# pixel.net
KiCad netlist of a schematic drawn in EAGLE
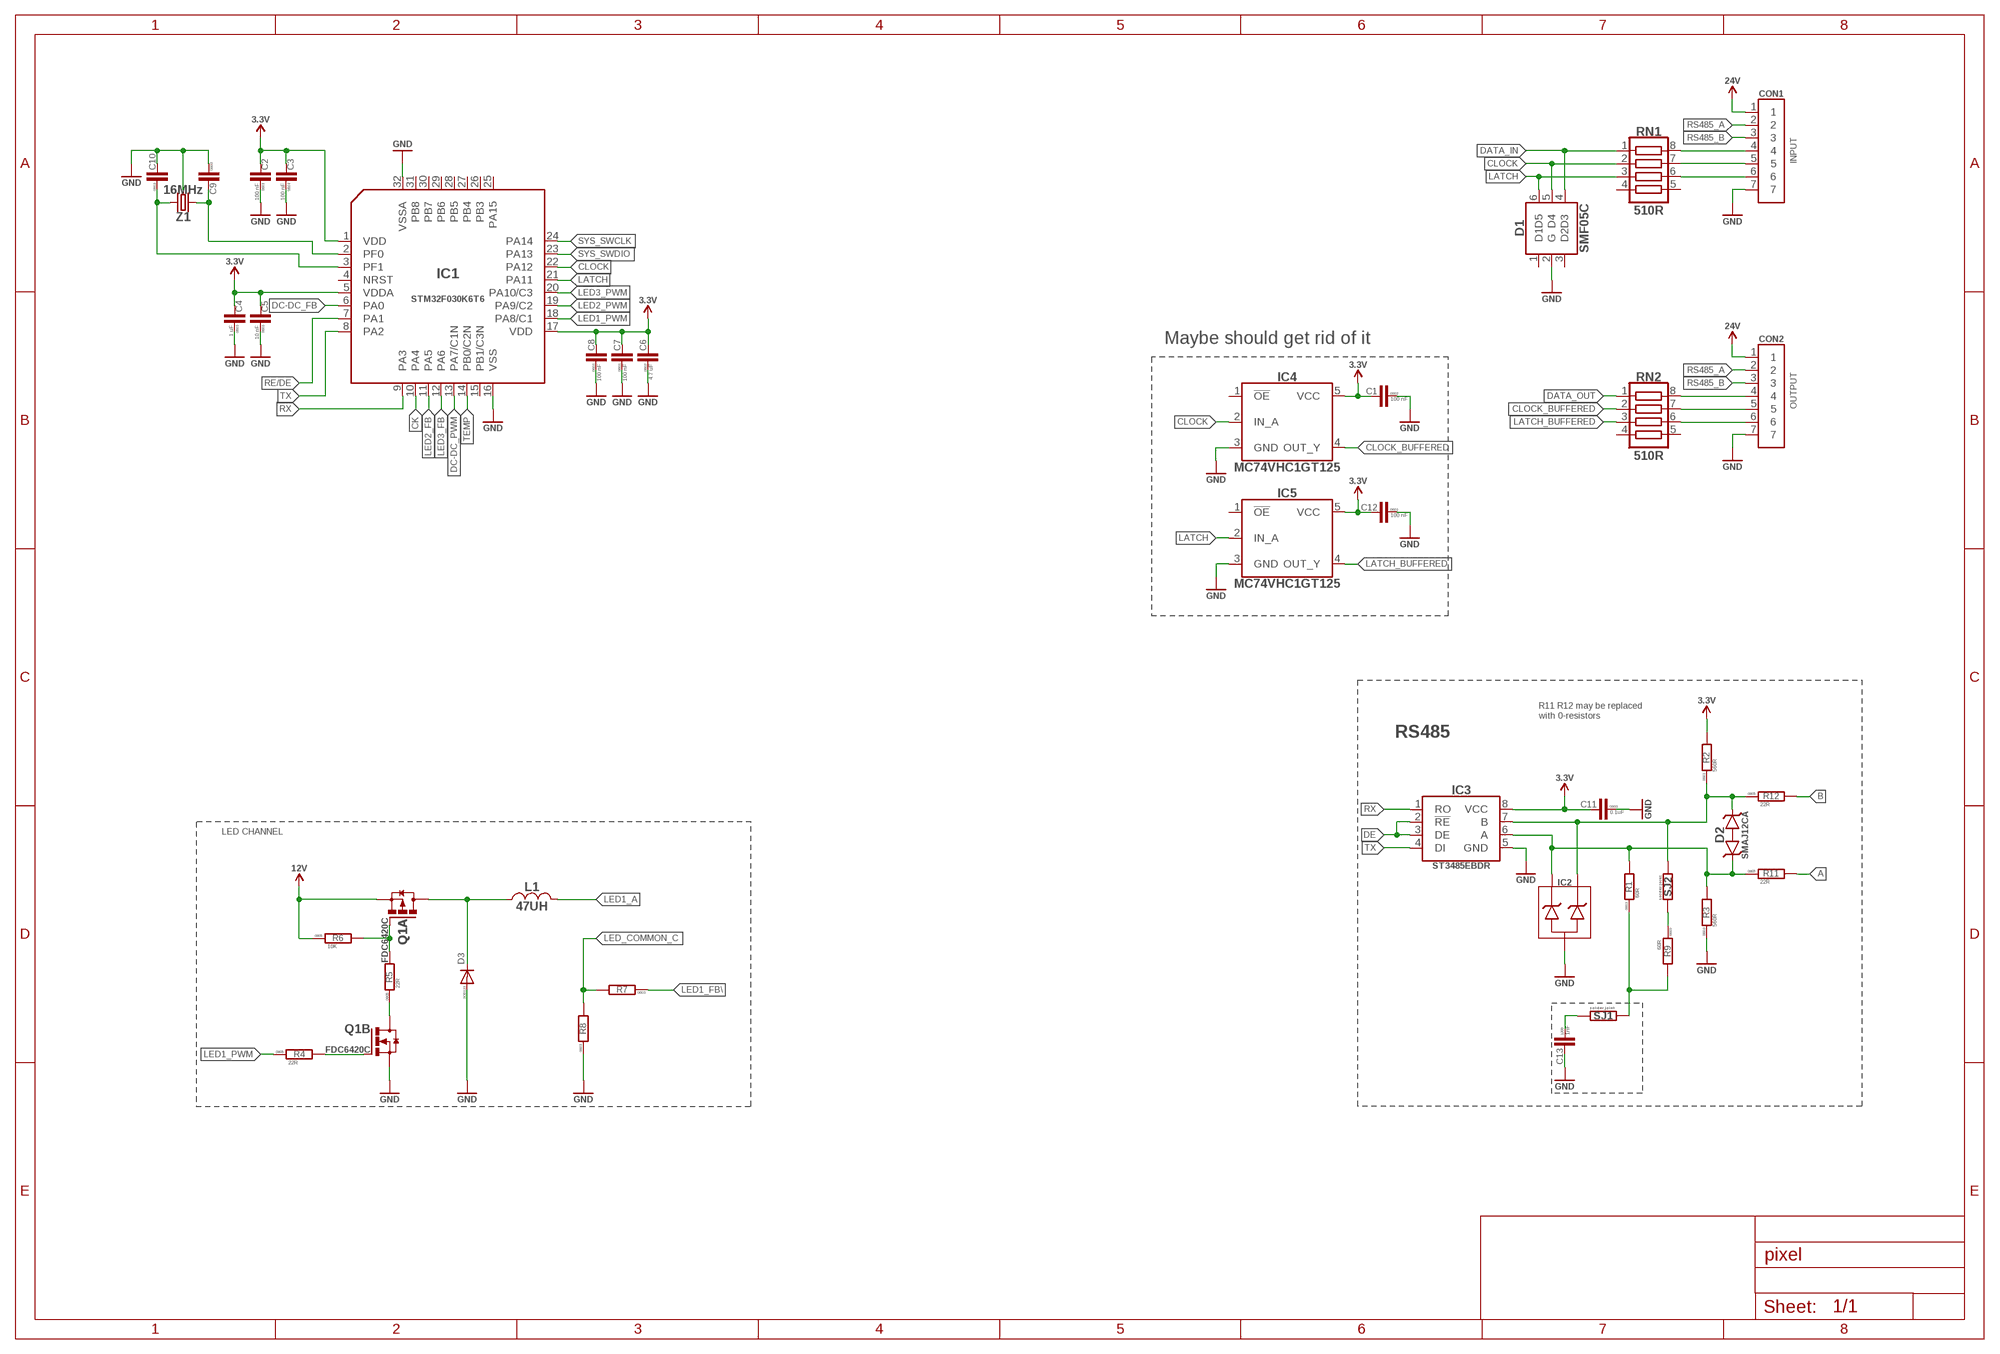
[diagram p0: schematic, sheet 1]

(export (version "E")
  (design (tool "Eeschema 10.0.6"))
  (components
    (comp (ref "C1")
      (value "100 nF")
      (footprint "eagle-import:C0603")
      (libsource (lib "eagle-import") (part "C-0603"))
    )
    (comp (ref "C2")
      (value "100 nF")
      (footprint "eagle-import:C0603")
      (libsource (lib "eagle-import") (part "C-0603"))
    )
    (comp (ref "C3")
      (value "100 nF")
      (footprint "eagle-import:C0603")
      (libsource (lib "eagle-import") (part "C-0603"))
    )
    (comp (ref "C4")
      (value "1 uF")
      (footprint "eagle-import:C0603")
      (libsource (lib "eagle-import") (part "C-0603"))
    )
    (comp (ref "C5")
      (value "10 nF")
      (footprint "eagle-import:C0603")
      (libsource (lib "eagle-import") (part "C-0603"))
    )
    (comp (ref "C6")
      (value "4.7 uF")
      (footprint "eagle-import:C0603")
      (libsource (lib "eagle-import") (part "C-0603"))
    )
    (comp (ref "C7")
      (value "100 nF")
      (footprint "eagle-import:C0603")
      (libsource (lib "eagle-import") (part "C-0603"))
    )
    (comp (ref "C8")
      (value "100 nF")
      (footprint "eagle-import:C0603")
      (libsource (lib "eagle-import") (part "C-0603"))
    )
    (comp (ref "C9")
      (value "C-0603")
      (footprint "eagle-import:C0603")
      (libsource (lib "eagle-import") (part "C-0603"))
    )
    (comp (ref "C10")
      (value "C-0603")
      (footprint "eagle-import:C0603")
      (libsource (lib "eagle-import") (part "C-0603"))
    )
    (comp (ref "C11")
      (value "0.1uF")
      (footprint "eagle-import:C0603")
      (libsource (lib "eagle-import") (part "C-0603"))
    )
    (comp (ref "C12")
      (value "100 nF")
      (footprint "eagle-import:C0603")
      (libsource (lib "eagle-import") (part "C-0603"))
    )
    (comp (ref "C13")
      (value "1nF")
      (footprint "eagle-import:C1206")
      (fields (field (name "ASSEMBLY") "SPECIAL"))
      (libsource (lib "eagle-import") (part "C-1206"))
    )
    (comp (ref "CON1")
      (value "DS1066-07M-SIDE")
      (footprint "eagle-import:DS1066-08M_SIDE")
      (libsource (lib "eagle-import") (part "DS1066-07M-SIDE"))
    )
    (comp (ref "CON2")
      (value "DS1066-07M-SIDE")
      (footprint "eagle-import:DS1066-08M_SIDE")
      (libsource (lib "eagle-import") (part "DS1066-07M-SIDE"))
    )
    (comp (ref "D1")
      (value "SMF05C")
      (footprint "eagle-import:SC70_6L")
      (fields (field (name "MANF") "Semtech Corporation"))
      (libsource (lib "eagle-import") (part "SMF05C"))
    )
    (comp (ref "D2")
      (value "SMAJ12A")
      (footprint "eagle-import:SMA")
      (fields (field (name "MANF") "Bourns Inc"))
      (libsource (lib "eagle-import") (part "SMAJ12A"))
    )
    (comp (ref "D3")
      (value "DIODE-SOD123")
      (footprint "eagle-import:SOD123")
      (libsource (lib "eagle-import") (part "DIODE-SOD123"))
    )
    (comp (ref "IC1")
      (value "STM32F030K6TX-LQFP32(7X7)")
      (footprint "eagle-import:LQFP32-7X7")
      (fields (field (name "MANF") "STMicroelectronics"))
      (libsource (lib "eagle-import") (part "STM32F030K6TX-LQFP32(7X7)"))
    )
    (comp (ref "IC2")
      (value "ESDA6V1L")
      (footprint "eagle-import:SOT23")
      (fields (field (name "MANF") "STMicroelectronics"))
      (libsource (lib "eagle-import") (part "ESDA6V1L"))
    )
    (comp (ref "IC3")
      (value "ST3485SOIC8")
      (footprint "eagle-import:SOIC8")
      (fields (field (name "MANF") "STMicroelectronics"))
      (libsource (lib "eagle-import") (part "ST3485SOIC8"))
    )
    (comp (ref "IC4")
      (value "MC74VHC1GT125")
      (footprint "eagle-import:SOT23-5")
      (fields (field (name "MANF") "ON Semiconductor"))
      (libsource (lib "eagle-import") (part "MC74VHC1GT125"))
    )
    (comp (ref "IC5")
      (value "MC74VHC1GT125")
      (footprint "eagle-import:SOT23-5")
      (fields (field (name "MANF") "ON Semiconductor"))
      (libsource (lib "eagle-import") (part "MC74VHC1GT125"))
    )
    (comp (ref "L1")
      (value "47UH")
      (footprint "eagle-import:SDR0604")
      (fields (field (name "MANF") "Bourns Inc"))
      (libsource (lib "eagle-import") (part "SDR0604-470KL"))
    )
    (comp (ref "Q1")
      (value "FDC6420C")
      (footprint "eagle-import:SOT23-6")
      (fields (field (name "MANF") "Fairchild"))
      (libsource (lib "eagle-import") (part "FDC6420C"))
    )
    (comp (ref "R1")
      (value "60R")
      (footprint "eagle-import:R0603")
      (libsource (lib "eagle-import") (part "R-0603"))
    )
    (comp (ref "R2")
      (value "560R")
      (footprint "eagle-import:R0603")
      (libsource (lib "eagle-import") (part "R-0603"))
    )
    (comp (ref "R3")
      (value "560R")
      (footprint "eagle-import:R0603")
      (libsource (lib "eagle-import") (part "R-0603"))
    )
    (comp (ref "R4")
      (value "22R")
      (footprint "eagle-import:R0805")
      (libsource (lib "eagle-import") (part "R-0805"))
    )
    (comp (ref "R5")
      (value "22R")
      (footprint "eagle-import:R0805")
      (libsource (lib "eagle-import") (part "R-0805"))
    )
    (comp (ref "R6")
      (value "10K")
      (footprint "eagle-import:R0805")
      (libsource (lib "eagle-import") (part "R-0805"))
    )
    (comp (ref "R7")
      (value "R-0603")
      (footprint "eagle-import:R0603")
      (libsource (lib "eagle-import") (part "R-0603"))
    )
    (comp (ref "R8")
      (value "R-0603")
      (footprint "eagle-import:R0603")
      (libsource (lib "eagle-import") (part "R-0603"))
    )
    (comp (ref "R9")
      (value "60R")
      (footprint "eagle-import:R0603")
      (libsource (lib "eagle-import") (part "R-0603"))
    )
    (comp (ref "R11")
      (value "22R")
      (footprint "eagle-import:R0805")
      (libsource (lib "eagle-import") (part "R-0805"))
    )
    (comp (ref "R12")
      (value "22R")
      (footprint "eagle-import:R0805")
      (libsource (lib "eagle-import") (part "R-0805"))
    )
    (comp (ref "RN1")
      (value "510R")
      (footprint "eagle-import:CAT16-J4")
      (fields
        (field (name "DIGIKEY#") "CAT16-511J4LF-ND")
        (field (name "MANF") "Bourns Inc")
        (field (name "MANF#") "CAT16-511J4LF")
      )
      (libsource (lib "eagle-import") (part "RESISTOR_ARRAY"))
    )
    (comp (ref "RN2")
      (value "510R")
      (footprint "eagle-import:CAT16-J4")
      (fields
        (field (name "DIGIKEY#") "CAT16-511J4LF-ND")
        (field (name "MANF") "Bourns Inc")
        (field (name "MANF#") "CAT16-511J4LF")
      )
      (libsource (lib "eagle-import") (part "RESISTOR_ARRAY"))
    )
    (comp (ref "SJ1")
      (value "SOLDER_JOINT")
      (footprint "eagle-import:RES_0")
      (libsource (lib "eagle-import") (part "SOLDER_JOINT"))
    )
    (comp (ref "SJ2")
      (value "SOLDER_JOINT")
      (footprint "eagle-import:RES_0")
      (libsource (lib "eagle-import") (part "SOLDER_JOINT"))
    )
    (comp (ref "Z1")
      (value "16MHz")
      (footprint "eagle-import:OSCILLATOR-3.2X2.5")
      (fields (field (name "MANF") "AVX Corp/Kyocera Corp"))
      (libsource (lib "eagle-import") (part "CRYSTAL-3.2X2.5-4P"))
    )
  )
  (nets
    (net (code "1") (name "3.3V") (class "Default")
      (node (ref "C1") (pin "2") (pinfunction "2_2") (pintype "passive"))
      (node (ref "C11") (pin "2") (pinfunction "2_2") (pintype "passive"))
      (node (ref "C12") (pin "2") (pinfunction "2_2") (pintype "passive"))
      (node (ref "C2") (pin "2") (pinfunction "2_2") (pintype "passive"))
      (node (ref "C3") (pin "2") (pinfunction "2_2") (pintype "passive"))
      (node (ref "C4") (pin "2") (pinfunction "2_2") (pintype "passive"))
      (node (ref "C5") (pin "2") (pinfunction "2_2") (pintype "passive"))
      (node (ref "C6") (pin "2") (pinfunction "2_2") (pintype "passive"))
      (node (ref "C7") (pin "2") (pinfunction "2_2") (pintype "passive"))
      (node (ref "C8") (pin "2") (pinfunction "2_2") (pintype "passive"))
      (node (ref "IC1") (pin "1") (pinfunction "VDD_1") (pintype "bidirectional"))
      (node (ref "IC1") (pin "17") (pinfunction "VDD_17") (pintype "bidirectional"))
      (node (ref "IC1") (pin "5") (pinfunction "VDDA_5") (pintype "bidirectional"))
      (node (ref "IC3") (pin "8") (pinfunction "VCC_8") (pintype "bidirectional"))
      (node (ref "IC4") (pin "5") (pinfunction "VCC_5") (pintype "bidirectional"))
      (node (ref "IC5") (pin "5") (pinfunction "VCC_5") (pintype "bidirectional"))
      (node (ref "R2") (pin "2") (pinfunction "2_2") (pintype "passive"))
    )
    (net (code "2") (name "12V") (class "Default")
      (node (ref "Q1") (pin "4") (pinfunction "S_4") (pintype "passive"))
      (node (ref "R6") (pin "1") (pinfunction "1_1") (pintype "passive"))
    )
    (net (code "3") (name "24V") (class "Default")
      (node (ref "CON1") (pin "1") (pinfunction "1_1") (pintype "bidirectional"))
      (node (ref "CON2") (pin "1") (pinfunction "1_1") (pintype "bidirectional"))
    )
    (net (code "4") (name "A") (class "Default")
      (node (ref "D2") (pin "A") (pinfunction "P$1_A") (pintype "bidirectional"))
      (node (ref "IC2") (pin "2") (pinfunction "C1_2") (pintype "bidirectional"))
      (node (ref "IC3") (pin "6") (pinfunction "A_6") (pintype "bidirectional"))
      (node (ref "R1") (pin "2") (pinfunction "2_2") (pintype "passive"))
      (node (ref "R11") (pin "1") (pinfunction "1_1") (pintype "passive"))
      (node (ref "R11") (pin "2") (pinfunction "2_2") (pintype "passive"))
      (node (ref "R3") (pin "2") (pinfunction "2_2") (pintype "passive"))
    )
    (net (code "5") (name "B") (class "Default")
      (node (ref "D2") (pin "C") (pinfunction "P$2_C") (pintype "bidirectional"))
      (node (ref "IC2") (pin "3") (pinfunction "C2_3") (pintype "bidirectional"))
      (node (ref "IC3") (pin "7") (pinfunction "B_7") (pintype "bidirectional"))
      (node (ref "R12") (pin "1") (pinfunction "1_1") (pintype "passive"))
      (node (ref "R12") (pin "2") (pinfunction "2_2") (pintype "passive"))
      (node (ref "R2") (pin "1") (pinfunction "1_1") (pintype "passive"))
      (node (ref "SJ2") (pin "1") (pinfunction "1_1") (pintype "passive"))
    )
    (net (code "6") (name "CK") (class "Default")
      (node (ref "IC1") (pin "10") (pinfunction "PA4_10") (pintype "bidirectional"))
    )
    (net (code "7") (name "CLOCK") (class "Default")
      (node (ref "D1") (pin "5") (pinfunction "D4_5") (pintype "bidirectional"))
      (node (ref "IC1") (pin "22") (pinfunction "PA12_22") (pintype "bidirectional"))
      (node (ref "IC4") (pin "2") (pinfunction "IN_A_2") (pintype "bidirectional"))
      (node (ref "RN1") (pin "2") (pinfunction "2_2") (pintype "passive"))
    )
    (net (code "8") (name "CLOCK_BUFFERED") (class "Default")
      (node (ref "IC4") (pin "4") (pinfunction "OUT_Y_4") (pintype "bidirectional"))
      (node (ref "RN2") (pin "2") (pinfunction "2_2") (pintype "passive"))
    )
    (net (code "9") (name "DATA_IN") (class "Default")
      (node (ref "D1") (pin "4") (pinfunction "D3_4") (pintype "bidirectional"))
      (node (ref "RN1") (pin "1") (pinfunction "1_1") (pintype "passive"))
    )
    (net (code "10") (name "DATA_OUT") (class "Default")
      (node (ref "RN2") (pin "1") (pinfunction "1_1") (pintype "passive"))
    )
    (net (code "11") (name "DC-DC_FB") (class "Default")
      (node (ref "IC1") (pin "6") (pinfunction "PA0_6") (pintype "bidirectional"))
    )
    (net (code "12") (name "DC-DC_PWM") (class "Default")
      (node (ref "IC1") (pin "13") (pinfunction "PA7/C1N_13") (pintype "bidirectional"))
    )
    (net (code "13") (name "DE") (class "Default")
      (node (ref "IC3") (pin "2") (pinfunction "~{RE}_2") (pintype "bidirectional"))
      (node (ref "IC3") (pin "3") (pinfunction "DE_3") (pintype "bidirectional"))
    )
    (net (code "14") (name "GND") (class "Default")
      (node (ref "C1") (pin "1") (pinfunction "1_1") (pintype "passive"))
      (node (ref "C10") (pin "2") (pinfunction "2_2") (pintype "passive"))
      (node (ref "C11") (pin "1") (pinfunction "1_1") (pintype "passive"))
      (node (ref "C12") (pin "1") (pinfunction "1_1") (pintype "passive"))
      (node (ref "C13") (pin "P$2") (pinfunction "2_P$2") (pintype "passive"))
      (node (ref "C2") (pin "1") (pinfunction "1_1") (pintype "passive"))
      (node (ref "C3") (pin "1") (pinfunction "1_1") (pintype "passive"))
      (node (ref "C4") (pin "1") (pinfunction "1_1") (pintype "passive"))
      (node (ref "C5") (pin "1") (pinfunction "1_1") (pintype "passive"))
      (node (ref "C6") (pin "1") (pinfunction "1_1") (pintype "passive"))
      (node (ref "C7") (pin "1") (pinfunction "1_1") (pintype "passive"))
      (node (ref "C8") (pin "1") (pinfunction "1_1") (pintype "passive"))
      (node (ref "C9") (pin "1") (pinfunction "1_1") (pintype "passive"))
      (node (ref "CON1") (pin "7") (pinfunction "7_7") (pintype "bidirectional"))
      (node (ref "CON2") (pin "7") (pinfunction "7_7") (pintype "bidirectional"))
      (node (ref "D1") (pin "2") (pinfunction "G_2") (pintype "bidirectional"))
      (node (ref "D3") (pin "A") (pinfunction "A_A") (pintype "passive"))
      (node (ref "IC1") (pin "16") (pinfunction "VSS_16") (pintype "bidirectional"))
      (node (ref "IC1") (pin "32") (pinfunction "VSSA_32") (pintype "bidirectional"))
      (node (ref "IC2") (pin "1") (pinfunction "A_1") (pintype "bidirectional"))
      (node (ref "IC3") (pin "5") (pinfunction "GND_5") (pintype "bidirectional"))
      (node (ref "IC4") (pin "3") (pinfunction "GND_3") (pintype "bidirectional"))
      (node (ref "IC5") (pin "3") (pinfunction "GND_3") (pintype "bidirectional"))
      (node (ref "Q1") (pin "5") (pinfunction "S_5") (pintype "passive"))
      (node (ref "R3") (pin "1") (pinfunction "1_1") (pintype "passive"))
      (node (ref "R8") (pin "1") (pinfunction "1_1") (pintype "passive"))
      (node (ref "Z1") (pin "2") (pinfunction "GND_2") (pintype "bidirectional"))
      (node (ref "Z1") (pin "4") (pinfunction "GND_4") (pintype "bidirectional"))
    )
    (net (code "15") (name "LATCH") (class "Default")
      (node (ref "D1") (pin "6") (pinfunction "D5_6") (pintype "bidirectional"))
      (node (ref "IC1") (pin "21") (pinfunction "PA11_21") (pintype "bidirectional"))
      (node (ref "IC5") (pin "2") (pinfunction "IN_A_2") (pintype "bidirectional"))
      (node (ref "RN1") (pin "3") (pinfunction "3_3") (pintype "passive"))
    )
    (net (code "16") (name "LATCH_BUFFERED") (class "Default")
      (node (ref "IC5") (pin "4") (pinfunction "OUT_Y_4") (pintype "bidirectional"))
      (node (ref "RN2") (pin "3") (pinfunction "3_3") (pintype "passive"))
    )
    (net (code "17") (name "LED1_A") (class "Default")
      (node (ref "L1") (pin "2") (pinfunction "2_2") (pintype "passive"))
    )
    (net (code "18") (name "LED1_FB\\") (class "Default")
      (node (ref "R7") (pin "1") (pinfunction "1_1") (pintype "passive"))
    )
    (net (code "19") (name "LED1_PWM") (class "Default")
      (node (ref "IC1") (pin "18") (pinfunction "PA8/C1_18") (pintype "bidirectional"))
      (node (ref "R4") (pin "1") (pinfunction "1_1") (pintype "passive"))
    )
    (net (code "20") (name "LED2_FB") (class "Default")
      (node (ref "IC1") (pin "11") (pinfunction "PA5_11") (pintype "bidirectional"))
    )
    (net (code "21") (name "LED2_PWM") (class "Default")
      (node (ref "IC1") (pin "19") (pinfunction "PA9/C2_19") (pintype "bidirectional"))
    )
    (net (code "22") (name "LED3_FB") (class "Default")
      (node (ref "IC1") (pin "12") (pinfunction "PA6_12") (pintype "bidirectional"))
    )
    (net (code "23") (name "LED3_PWM") (class "Default")
      (node (ref "IC1") (pin "20") (pinfunction "PA10/C3_20") (pintype "bidirectional"))
    )
    (net (code "24") (name "LED_COMMON_C") (class "Default")
      (node (ref "R7") (pin "2") (pinfunction "2_2") (pintype "passive"))
      (node (ref "R8") (pin "2") (pinfunction "2_2") (pintype "passive"))
    )
    (net (code "25") (name "Net-(C13-1)") (class "Default")
      (node (ref "C13") (pin "P$1") (pinfunction "1_P$1") (pintype "passive"))
      (node (ref "SJ1") (pin "2") (pinfunction "2_2") (pintype "passive"))
    )
    (net (code "26") (name "Net-(CON1-Pad4)") (class "Default")
      (node (ref "CON1") (pin "4") (pinfunction "4_4") (pintype "bidirectional"))
      (node (ref "RN1") (pin "8") (pinfunction "8_8") (pintype "passive"))
    )
    (net (code "27") (name "Net-(CON1-Pad5)") (class "Default")
      (node (ref "CON1") (pin "5") (pinfunction "5_5") (pintype "bidirectional"))
      (node (ref "RN1") (pin "7") (pinfunction "7_7") (pintype "passive"))
    )
    (net (code "28") (name "Net-(CON1-Pad6)") (class "Default")
      (node (ref "CON1") (pin "6") (pinfunction "6_6") (pintype "bidirectional"))
      (node (ref "RN1") (pin "6") (pinfunction "6_6") (pintype "passive"))
    )
    (net (code "29") (name "Net-(CON2-Pad4)") (class "Default")
      (node (ref "CON2") (pin "4") (pinfunction "4_4") (pintype "bidirectional"))
      (node (ref "RN2") (pin "8") (pinfunction "8_8") (pintype "passive"))
    )
    (net (code "30") (name "Net-(CON2-Pad5)") (class "Default")
      (node (ref "CON2") (pin "5") (pinfunction "5_5") (pintype "bidirectional"))
      (node (ref "RN2") (pin "7") (pinfunction "7_7") (pintype "passive"))
    )
    (net (code "31") (name "Net-(CON2-Pad6)") (class "Default")
      (node (ref "CON2") (pin "6") (pinfunction "6_6") (pintype "bidirectional"))
      (node (ref "RN2") (pin "6") (pinfunction "6_6") (pintype "passive"))
    )
    (net (code "32") (name "Net-(IC1-PF0)") (class "Default")
      (node (ref "C9") (pin "2") (pinfunction "2_2") (pintype "passive"))
      (node (ref "IC1") (pin "2") (pinfunction "PF0_2") (pintype "bidirectional"))
      (node (ref "Z1") (pin "1") (pinfunction "1_1") (pintype "passive"))
    )
    (net (code "33") (name "Net-(IC1-PF1)") (class "Default")
      (node (ref "C10") (pin "1") (pinfunction "1_1") (pintype "passive"))
      (node (ref "IC1") (pin "3") (pinfunction "PF1_3") (pintype "bidirectional"))
      (node (ref "Z1") (pin "3") (pinfunction "2_3") (pintype "passive"))
    )
    (net (code "34") (name "Net-(Q1A-D)") (class "Default")
      (node (ref "D3") (pin "C") (pinfunction "C_C") (pintype "passive"))
      (node (ref "L1") (pin "1") (pinfunction "1_1") (pintype "passive"))
      (node (ref "Q1") (pin "2") (pinfunction "D_2") (pintype "passive"))
    )
    (net (code "35") (name "Net-(Q1A-G)") (class "Default")
      (node (ref "Q1") (pin "3") (pinfunction "G_3") (pintype "passive"))
      (node (ref "R5") (pin "2") (pinfunction "2_2") (pintype "passive"))
      (node (ref "R6") (pin "2") (pinfunction "2_2") (pintype "passive"))
    )
    (net (code "36") (name "Net-(Q1B-D)") (class "Default")
      (node (ref "Q1") (pin "6") (pinfunction "D_6") (pintype "passive"))
      (node (ref "R5") (pin "1") (pinfunction "1_1") (pintype "passive"))
    )
    (net (code "37") (name "Net-(Q1B-G)") (class "Default")
      (node (ref "Q1") (pin "1") (pinfunction "G_1") (pintype "passive"))
      (node (ref "R4") (pin "2") (pinfunction "2_2") (pintype "passive"))
    )
    (net (code "38") (name "Net-(R1-Pad1)") (class "Default")
      (node (ref "R1") (pin "1") (pinfunction "1_1") (pintype "passive"))
      (node (ref "R9") (pin "2") (pinfunction "2_2") (pintype "passive"))
      (node (ref "SJ1") (pin "1") (pinfunction "1_1") (pintype "passive"))
    )
    (net (code "39") (name "Net-(R9-Pad1)") (class "Default")
      (node (ref "R9") (pin "1") (pinfunction "1_1") (pintype "passive"))
      (node (ref "SJ2") (pin "2") (pinfunction "2_2") (pintype "passive"))
    )
    (net (code "40") (name "RE{slash}DE") (class "Default")
      (node (ref "IC1") (pin "7") (pinfunction "PA1_7") (pintype "bidirectional"))
    )
    (net (code "41") (name "RS485_A") (class "Default")
      (node (ref "CON1") (pin "2") (pinfunction "2_2") (pintype "bidirectional"))
      (node (ref "CON2") (pin "2") (pinfunction "2_2") (pintype "bidirectional"))
    )
    (net (code "42") (name "RS485_B") (class "Default")
      (node (ref "CON1") (pin "3") (pinfunction "3_3") (pintype "bidirectional"))
      (node (ref "CON2") (pin "3") (pinfunction "3_3") (pintype "bidirectional"))
    )
    (net (code "43") (name "RX") (class "Default")
      (node (ref "IC1") (pin "9") (pinfunction "PA3_9") (pintype "bidirectional"))
      (node (ref "IC3") (pin "1") (pinfunction "RO_1") (pintype "bidirectional"))
    )
    (net (code "44") (name "SYS_SWCLK") (class "Default")
      (node (ref "IC1") (pin "24") (pinfunction "PA14_24") (pintype "bidirectional"))
    )
    (net (code "45") (name "SYS_SWDIO") (class "Default")
      (node (ref "IC1") (pin "23") (pinfunction "PA13_23") (pintype "bidirectional"))
    )
    (net (code "46") (name "TEMP") (class "Default")
      (node (ref "IC1") (pin "14") (pinfunction "PB0/C2N_14") (pintype "bidirectional"))
    )
    (net (code "47") (name "TX") (class "Default")
      (node (ref "IC1") (pin "8") (pinfunction "PA2_8") (pintype "bidirectional"))
      (node (ref "IC3") (pin "4") (pinfunction "DI_4") (pintype "bidirectional"))
    )
    (net (code "48") (name "unconnected-(D1-D1-Pad1)") (class "Default")
      (node (ref "D1") (pin "1") (pinfunction "D1_1") (pintype "bidirectional"))
    )
    (net (code "49") (name "unconnected-(D1-D2-Pad3)") (class "Default")
      (node (ref "D1") (pin "3") (pinfunction "D2_3") (pintype "bidirectional"))
    )
    (net (code "50") (name "unconnected-(IC1-NRST-Pad4)") (class "Default")
      (node (ref "IC1") (pin "4") (pinfunction "NRST_4") (pintype "bidirectional"))
    )
    (net (code "51") (name "unconnected-(IC1-PA15-Pad25)") (class "Default")
      (node (ref "IC1") (pin "25") (pinfunction "PA15_25") (pintype "bidirectional"))
    )
    (net (code "52") (name "unconnected-(IC1-PB1{slash}C3N-Pad15)") (class "Default")
      (node (ref "IC1") (pin "15") (pinfunction "PB1/C3N_15") (pintype "bidirectional"))
    )
    (net (code "53") (name "unconnected-(IC1-PB3-Pad26)") (class "Default")
      (node (ref "IC1") (pin "26") (pinfunction "PB3_26") (pintype "bidirectional"))
    )
    (net (code "54") (name "unconnected-(IC1-PB4-Pad27)") (class "Default")
      (node (ref "IC1") (pin "27") (pinfunction "PB4_27") (pintype "bidirectional"))
    )
    (net (code "55") (name "unconnected-(IC1-PB5-Pad28)") (class "Default")
      (node (ref "IC1") (pin "28") (pinfunction "PB5_28") (pintype "bidirectional"))
    )
    (net (code "56") (name "unconnected-(IC1-PB6-Pad29)") (class "Default")
      (node (ref "IC1") (pin "29") (pinfunction "PB6_29") (pintype "bidirectional"))
    )
    (net (code "57") (name "unconnected-(IC1-PB7-Pad30)") (class "Default")
      (node (ref "IC1") (pin "30") (pinfunction "PB7_30") (pintype "bidirectional"))
    )
    (net (code "58") (name "unconnected-(IC1-PB8-Pad31)") (class "Default")
      (node (ref "IC1") (pin "31") (pinfunction "PB8_31") (pintype "bidirectional"))
    )
    (net (code "59") (name "unconnected-(IC4-~{OE}-Pad1)") (class "Default")
      (node (ref "IC4") (pin "1") (pinfunction "~{OE}_1") (pintype "bidirectional"))
    )
    (net (code "60") (name "unconnected-(IC5-~{OE}-Pad1)") (class "Default")
      (node (ref "IC5") (pin "1") (pinfunction "~{OE}_1") (pintype "bidirectional"))
    )
    (net (code "61") (name "unconnected-(RN1-Pad4)") (class "Default")
      (node (ref "RN1") (pin "4") (pinfunction "4_4") (pintype "passive"))
    )
    (net (code "62") (name "unconnected-(RN1-Pad5)") (class "Default")
      (node (ref "RN1") (pin "5") (pinfunction "5_5") (pintype "passive"))
    )
    (net (code "63") (name "unconnected-(RN2-Pad4)") (class "Default")
      (node (ref "RN2") (pin "4") (pinfunction "4_4") (pintype "passive"))
    )
    (net (code "64") (name "unconnected-(RN2-Pad5)") (class "Default")
      (node (ref "RN2") (pin "5") (pinfunction "5_5") (pintype "passive"))
    )
  )
)
